# untitled.net
KiCad netlist of a schematic drawn in EAGLE
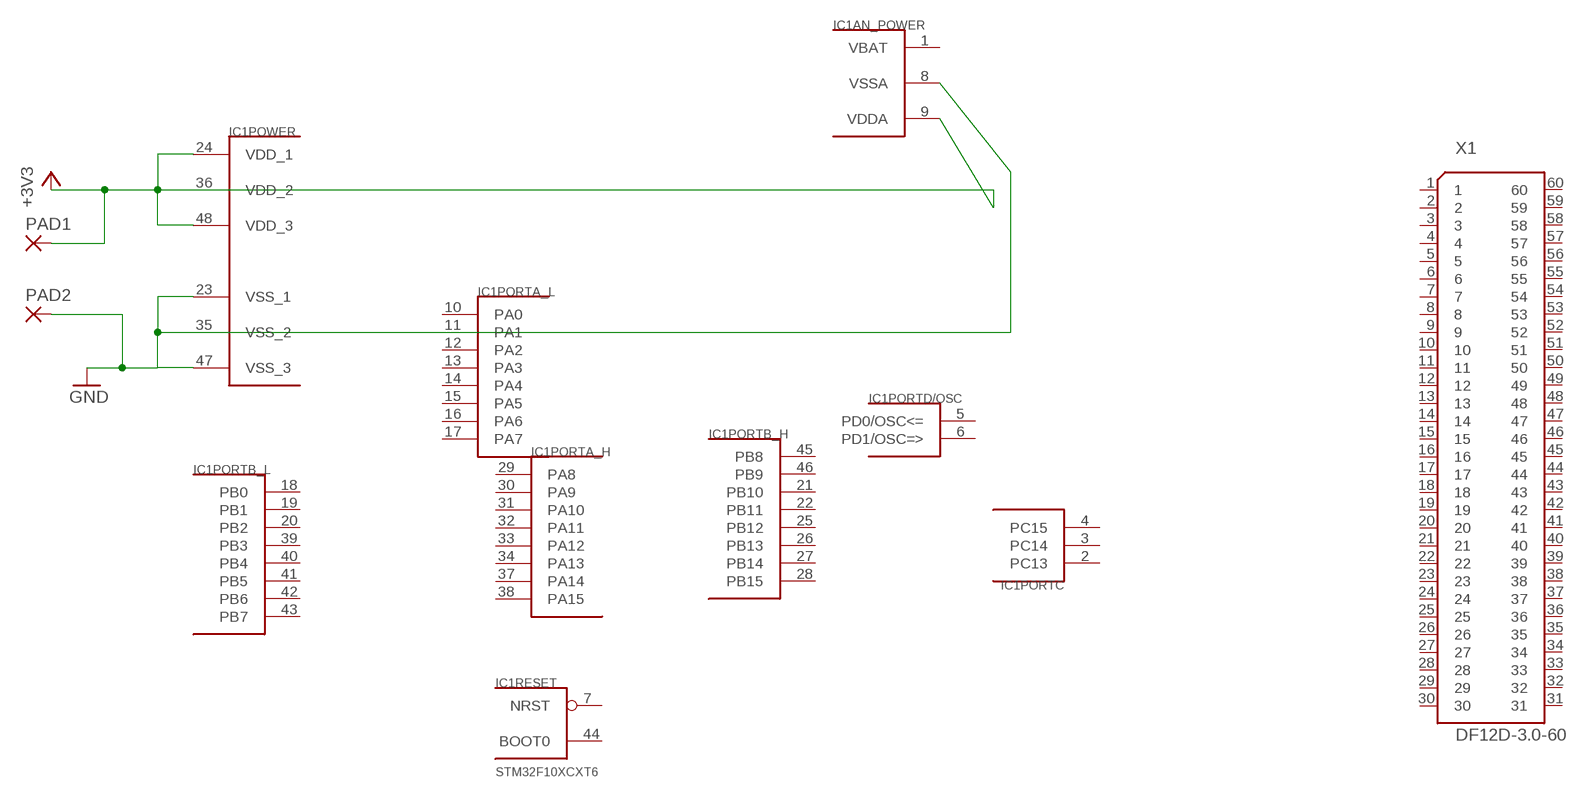
[diagram p0: schematic, sheet 1]

(export (version "E")
  (design (tool "Eeschema 10.0.6"))
  (components
    (comp (ref "IC1")
      (value "STM32F10XCXT6")
      (footprint "eagle-import:TQFP48")
      (libsource (lib "eagle-import") (part "STM32F10XCXT6"))
    )
    (comp (ref "PAD1")
      (value "1,6/0,8")
      (footprint "eagle-import:1,6_0,8")
      (libsource (lib "eagle-import") (part "1,6/0,8"))
    )
    (comp (ref "PAD2")
      (value "1,6/0,8")
      (footprint "eagle-import:1,6_0,8")
      (libsource (lib "eagle-import") (part "1,6/0,8"))
    )
    (comp (ref "X1")
      (value "DF12D-3.0-60")
      (footprint "eagle-import:DF12-3.0-60")
      (libsource (lib "eagle-import") (part "DF12D-3.0-60"))
    )
  )
  (nets
    (net (code "1") (name "+3V3") (class "Default")
      (node (ref "IC1") (pin "24") (pinfunction "VDD_1_24") (pintype "power_in"))
      (node (ref "IC1") (pin "36") (pinfunction "VDD_2_36") (pintype "power_in"))
      (node (ref "IC1") (pin "48") (pinfunction "VDD_3_48") (pintype "power_in"))
      (node (ref "IC1") (pin "9") (pinfunction "VDDA_9") (pintype "power_in"))
      (node (ref "PAD1") (pin "1") (pinfunction "P_1") (pintype "passive"))
    )
    (net (code "2") (name "/VBAT") (class "Default")
      (node (ref "IC1") (pin "1") (pinfunction "VBAT_1") (pintype "power_in"))
    )
    (net (code "3") (name "GND") (class "Default")
      (node (ref "IC1") (pin "23") (pinfunction "VSS_1_23") (pintype "power_in"))
      (node (ref "IC1") (pin "35") (pinfunction "VSS_2_35") (pintype "power_in"))
      (node (ref "IC1") (pin "47") (pinfunction "VSS_3_47") (pintype "power_in"))
      (node (ref "IC1") (pin "8") (pinfunction "VSSA_8") (pintype "power_in"))
      (node (ref "PAD2") (pin "1") (pinfunction "P_1") (pintype "passive"))
    )
    (net (code "4") (name "unconnected-(IC1B-PA8-Pad29)") (class "Default")
      (node (ref "IC1") (pin "29") (pinfunction "PA8_29") (pintype "bidirectional"))
    )
    (net (code "5") (name "unconnected-(IC1B-PA9-Pad30)") (class "Default")
      (node (ref "IC1") (pin "30") (pinfunction "PA9_30") (pintype "bidirectional"))
    )
    (net (code "6") (name "unconnected-(IC1B-PA10-Pad31)") (class "Default")
      (node (ref "IC1") (pin "31") (pinfunction "PA10_31") (pintype "bidirectional"))
    )
    (net (code "7") (name "unconnected-(IC1B-PA11-Pad32)") (class "Default")
      (node (ref "IC1") (pin "32") (pinfunction "PA11_32") (pintype "bidirectional"))
    )
    (net (code "8") (name "unconnected-(IC1B-PA12-Pad33)") (class "Default")
      (node (ref "IC1") (pin "33") (pinfunction "PA12_33") (pintype "bidirectional"))
    )
    (net (code "9") (name "unconnected-(IC1B-PA13-Pad34)") (class "Default")
      (node (ref "IC1") (pin "34") (pinfunction "PA13_34") (pintype "bidirectional"))
    )
    (net (code "10") (name "unconnected-(IC1B-PA14-Pad37)") (class "Default")
      (node (ref "IC1") (pin "37") (pinfunction "PA14_37") (pintype "bidirectional"))
    )
    (net (code "11") (name "unconnected-(IC1B-PA15-Pad38)") (class "Default")
      (node (ref "IC1") (pin "38") (pinfunction "PA15_38") (pintype "bidirectional"))
    )
    (net (code "12") (name "unconnected-(IC1C-PA0-Pad10)") (class "Default")
      (node (ref "IC1") (pin "10") (pinfunction "PA0_10") (pintype "bidirectional"))
    )
    (net (code "13") (name "unconnected-(IC1C-PA1-Pad11)") (class "Default")
      (node (ref "IC1") (pin "11") (pinfunction "PA1_11") (pintype "bidirectional"))
    )
    (net (code "14") (name "unconnected-(IC1C-PA2-Pad12)") (class "Default")
      (node (ref "IC1") (pin "12") (pinfunction "PA2_12") (pintype "bidirectional"))
    )
    (net (code "15") (name "unconnected-(IC1C-PA3-Pad13)") (class "Default")
      (node (ref "IC1") (pin "13") (pinfunction "PA3_13") (pintype "bidirectional"))
    )
    (net (code "16") (name "unconnected-(IC1C-PA4-Pad14)") (class "Default")
      (node (ref "IC1") (pin "14") (pinfunction "PA4_14") (pintype "bidirectional"))
    )
    (net (code "17") (name "unconnected-(IC1C-PA5-Pad15)") (class "Default")
      (node (ref "IC1") (pin "15") (pinfunction "PA5_15") (pintype "bidirectional"))
    )
    (net (code "18") (name "unconnected-(IC1C-PA6-Pad16)") (class "Default")
      (node (ref "IC1") (pin "16") (pinfunction "PA6_16") (pintype "bidirectional"))
    )
    (net (code "19") (name "unconnected-(IC1C-PA7-Pad17)") (class "Default")
      (node (ref "IC1") (pin "17") (pinfunction "PA7_17") (pintype "bidirectional"))
    )
    (net (code "20") (name "unconnected-(IC1D-PB8-Pad45)") (class "Default")
      (node (ref "IC1") (pin "45") (pinfunction "PB8_45") (pintype "bidirectional"))
    )
    (net (code "21") (name "unconnected-(IC1D-PB9-Pad46)") (class "Default")
      (node (ref "IC1") (pin "46") (pinfunction "PB9_46") (pintype "bidirectional"))
    )
    (net (code "22") (name "unconnected-(IC1D-PB10-Pad21)") (class "Default")
      (node (ref "IC1") (pin "21") (pinfunction "PB10_21") (pintype "bidirectional"))
    )
    (net (code "23") (name "unconnected-(IC1D-PB11-Pad22)") (class "Default")
      (node (ref "IC1") (pin "22") (pinfunction "PB11_22") (pintype "bidirectional"))
    )
    (net (code "24") (name "unconnected-(IC1D-PB12-Pad25)") (class "Default")
      (node (ref "IC1") (pin "25") (pinfunction "PB12_25") (pintype "bidirectional"))
    )
    (net (code "25") (name "unconnected-(IC1D-PB13-Pad26)") (class "Default")
      (node (ref "IC1") (pin "26") (pinfunction "PB13_26") (pintype "bidirectional"))
    )
    (net (code "26") (name "unconnected-(IC1D-PB14-Pad27)") (class "Default")
      (node (ref "IC1") (pin "27") (pinfunction "PB14_27") (pintype "bidirectional"))
    )
    (net (code "27") (name "unconnected-(IC1D-PB15-Pad28)") (class "Default")
      (node (ref "IC1") (pin "28") (pinfunction "PB15_28") (pintype "bidirectional"))
    )
    (net (code "28") (name "unconnected-(IC1E-PB0-Pad18)") (class "Default")
      (node (ref "IC1") (pin "18") (pinfunction "PB0_18") (pintype "bidirectional"))
    )
    (net (code "29") (name "unconnected-(IC1E-PB1-Pad19)") (class "Default")
      (node (ref "IC1") (pin "19") (pinfunction "PB1_19") (pintype "bidirectional"))
    )
    (net (code "30") (name "unconnected-(IC1E-PB2-Pad20)") (class "Default")
      (node (ref "IC1") (pin "20") (pinfunction "PB2_20") (pintype "bidirectional"))
    )
    (net (code "31") (name "unconnected-(IC1E-PB3-Pad39)") (class "Default")
      (node (ref "IC1") (pin "39") (pinfunction "PB3_39") (pintype "bidirectional"))
    )
    (net (code "32") (name "unconnected-(IC1E-PB4-Pad40)") (class "Default")
      (node (ref "IC1") (pin "40") (pinfunction "PB4_40") (pintype "bidirectional"))
    )
    (net (code "33") (name "unconnected-(IC1E-PB5-Pad41)") (class "Default")
      (node (ref "IC1") (pin "41") (pinfunction "PB5_41") (pintype "bidirectional"))
    )
    (net (code "34") (name "unconnected-(IC1E-PB6-Pad42)") (class "Default")
      (node (ref "IC1") (pin "42") (pinfunction "PB6_42") (pintype "bidirectional"))
    )
    (net (code "35") (name "unconnected-(IC1E-PB7-Pad43)") (class "Default")
      (node (ref "IC1") (pin "43") (pinfunction "PB7_43") (pintype "bidirectional"))
    )
    (net (code "36") (name "unconnected-(IC1F-PC13-Pad2)") (class "Default")
      (node (ref "IC1") (pin "2") (pinfunction "PC13_2") (pintype "bidirectional"))
    )
    (net (code "37") (name "unconnected-(IC1F-PC14-Pad3)") (class "Default")
      (node (ref "IC1") (pin "3") (pinfunction "PC14_3") (pintype "bidirectional"))
    )
    (net (code "38") (name "unconnected-(IC1F-PC15-Pad4)") (class "Default")
      (node (ref "IC1") (pin "4") (pinfunction "PC15_4") (pintype "bidirectional"))
    )
    (net (code "39") (name "unconnected-(IC1G-PD0{slash}OSC<=-Pad5)") (class "Default")
      (node (ref "IC1") (pin "5") (pinfunction "PD0/OSC<=_5") (pintype "bidirectional"))
    )
    (net (code "40") (name "unconnected-(IC1G-PD1{slash}OSC=>-Pad6)") (class "Default")
      (node (ref "IC1") (pin "6") (pinfunction "PD1/OSC=>_6") (pintype "bidirectional"))
    )
    (net (code "41") (name "unconnected-(IC1I-BOOT0-Pad44)") (class "Default")
      (node (ref "IC1") (pin "44") (pinfunction "BOOT0_44") (pintype "input"))
    )
    (net (code "42") (name "unconnected-(IC1I-NRST-Pad7)") (class "Default")
      (node (ref "IC1") (pin "7") (pinfunction "NRST_7") (pintype "input"))
    )
    (net (code "43") (name "unconnected-(X1-Pad1)") (class "Default")
      (node (ref "X1") (pin "1") (pinfunction "1_1") (pintype "bidirectional"))
    )
    (net (code "44") (name "unconnected-(X1-Pad2)") (class "Default")
      (node (ref "X1") (pin "2") (pinfunction "2_2") (pintype "bidirectional"))
    )
    (net (code "45") (name "unconnected-(X1-Pad3)") (class "Default")
      (node (ref "X1") (pin "3") (pinfunction "3_3") (pintype "bidirectional"))
    )
    (net (code "46") (name "unconnected-(X1-Pad4)") (class "Default")
      (node (ref "X1") (pin "4") (pinfunction "4_4") (pintype "bidirectional"))
    )
    (net (code "47") (name "unconnected-(X1-Pad5)") (class "Default")
      (node (ref "X1") (pin "5") (pinfunction "5_5") (pintype "bidirectional"))
    )
    (net (code "48") (name "unconnected-(X1-Pad6)") (class "Default")
      (node (ref "X1") (pin "6") (pinfunction "6_6") (pintype "bidirectional"))
    )
    (net (code "49") (name "unconnected-(X1-Pad7)") (class "Default")
      (node (ref "X1") (pin "7") (pinfunction "7_7") (pintype "bidirectional"))
    )
    (net (code "50") (name "unconnected-(X1-Pad8)") (class "Default")
      (node (ref "X1") (pin "8") (pinfunction "8_8") (pintype "bidirectional"))
    )
    (net (code "51") (name "unconnected-(X1-Pad9)") (class "Default")
      (node (ref "X1") (pin "9") (pinfunction "9_9") (pintype "bidirectional"))
    )
    (net (code "52") (name "unconnected-(X1-Pad10)") (class "Default")
      (node (ref "X1") (pin "10") (pinfunction "10_10") (pintype "bidirectional"))
    )
    (net (code "53") (name "unconnected-(X1-Pad11)") (class "Default")
      (node (ref "X1") (pin "11") (pinfunction "11_11") (pintype "bidirectional"))
    )
    (net (code "54") (name "unconnected-(X1-Pad12)") (class "Default")
      (node (ref "X1") (pin "12") (pinfunction "12_12") (pintype "bidirectional"))
    )
    (net (code "55") (name "unconnected-(X1-Pad13)") (class "Default")
      (node (ref "X1") (pin "13") (pinfunction "13_13") (pintype "bidirectional"))
    )
    (net (code "56") (name "unconnected-(X1-Pad14)") (class "Default")
      (node (ref "X1") (pin "14") (pinfunction "14_14") (pintype "bidirectional"))
    )
    (net (code "57") (name "unconnected-(X1-Pad15)") (class "Default")
      (node (ref "X1") (pin "15") (pinfunction "15_15") (pintype "bidirectional"))
    )
    (net (code "58") (name "unconnected-(X1-Pad16)") (class "Default")
      (node (ref "X1") (pin "16") (pinfunction "16_16") (pintype "bidirectional"))
    )
    (net (code "59") (name "unconnected-(X1-Pad17)") (class "Default")
      (node (ref "X1") (pin "17") (pinfunction "17_17") (pintype "bidirectional"))
    )
    (net (code "60") (name "unconnected-(X1-Pad18)") (class "Default")
      (node (ref "X1") (pin "18") (pinfunction "18_18") (pintype "bidirectional"))
    )
    (net (code "61") (name "unconnected-(X1-Pad19)") (class "Default")
      (node (ref "X1") (pin "19") (pinfunction "19_19") (pintype "bidirectional"))
    )
    (net (code "62") (name "unconnected-(X1-Pad20)") (class "Default")
      (node (ref "X1") (pin "20") (pinfunction "20_20") (pintype "bidirectional"))
    )
    (net (code "63") (name "unconnected-(X1-Pad21)") (class "Default")
      (node (ref "X1") (pin "21") (pinfunction "21_21") (pintype "bidirectional"))
    )
    (net (code "64") (name "unconnected-(X1-Pad22)") (class "Default")
      (node (ref "X1") (pin "22") (pinfunction "22_22") (pintype "bidirectional"))
    )
    (net (code "65") (name "unconnected-(X1-Pad23)") (class "Default")
      (node (ref "X1") (pin "23") (pinfunction "23_23") (pintype "bidirectional"))
    )
    (net (code "66") (name "unconnected-(X1-Pad24)") (class "Default")
      (node (ref "X1") (pin "24") (pinfunction "24_24") (pintype "bidirectional"))
    )
    (net (code "67") (name "unconnected-(X1-Pad25)") (class "Default")
      (node (ref "X1") (pin "25") (pinfunction "25_25") (pintype "bidirectional"))
    )
    (net (code "68") (name "unconnected-(X1-Pad26)") (class "Default")
      (node (ref "X1") (pin "26") (pinfunction "26_26") (pintype "bidirectional"))
    )
    (net (code "69") (name "unconnected-(X1-Pad27)") (class "Default")
      (node (ref "X1") (pin "27") (pinfunction "27_27") (pintype "bidirectional"))
    )
    (net (code "70") (name "unconnected-(X1-Pad28)") (class "Default")
      (node (ref "X1") (pin "28") (pinfunction "28_28") (pintype "bidirectional"))
    )
    (net (code "71") (name "unconnected-(X1-Pad29)") (class "Default")
      (node (ref "X1") (pin "29") (pinfunction "29_29") (pintype "bidirectional"))
    )
    (net (code "72") (name "unconnected-(X1-Pad30)") (class "Default")
      (node (ref "X1") (pin "30") (pinfunction "30_30") (pintype "bidirectional"))
    )
    (net (code "73") (name "unconnected-(X1-Pad31)") (class "Default")
      (node (ref "X1") (pin "31") (pinfunction "31_31") (pintype "bidirectional"))
    )
    (net (code "74") (name "unconnected-(X1-Pad32)") (class "Default")
      (node (ref "X1") (pin "32") (pinfunction "32_32") (pintype "bidirectional"))
    )
    (net (code "75") (name "unconnected-(X1-Pad33)") (class "Default")
      (node (ref "X1") (pin "33") (pinfunction "33_33") (pintype "bidirectional"))
    )
    (net (code "76") (name "unconnected-(X1-Pad34)") (class "Default")
      (node (ref "X1") (pin "34") (pinfunction "34_34") (pintype "bidirectional"))
    )
    (net (code "77") (name "unconnected-(X1-Pad35)") (class "Default")
      (node (ref "X1") (pin "35") (pinfunction "35_35") (pintype "bidirectional"))
    )
    (net (code "78") (name "unconnected-(X1-Pad36)") (class "Default")
      (node (ref "X1") (pin "36") (pinfunction "36_36") (pintype "bidirectional"))
    )
    (net (code "79") (name "unconnected-(X1-Pad37)") (class "Default")
      (node (ref "X1") (pin "37") (pinfunction "37_37") (pintype "bidirectional"))
    )
    (net (code "80") (name "unconnected-(X1-Pad38)") (class "Default")
      (node (ref "X1") (pin "38") (pinfunction "38_38") (pintype "bidirectional"))
    )
    (net (code "81") (name "unconnected-(X1-Pad39)") (class "Default")
      (node (ref "X1") (pin "39") (pinfunction "39_39") (pintype "bidirectional"))
    )
    (net (code "82") (name "unconnected-(X1-Pad40)") (class "Default")
      (node (ref "X1") (pin "40") (pinfunction "40_40") (pintype "bidirectional"))
    )
    (net (code "83") (name "unconnected-(X1-Pad41)") (class "Default")
      (node (ref "X1") (pin "41") (pinfunction "41_41") (pintype "bidirectional"))
    )
    (net (code "84") (name "unconnected-(X1-Pad42)") (class "Default")
      (node (ref "X1") (pin "42") (pinfunction "42_42") (pintype "bidirectional"))
    )
    (net (code "85") (name "unconnected-(X1-Pad43)") (class "Default")
      (node (ref "X1") (pin "43") (pinfunction "43_43") (pintype "bidirectional"))
    )
    (net (code "86") (name "unconnected-(X1-Pad44)") (class "Default")
      (node (ref "X1") (pin "44") (pinfunction "44_44") (pintype "bidirectional"))
    )
    (net (code "87") (name "unconnected-(X1-Pad45)") (class "Default")
      (node (ref "X1") (pin "45") (pinfunction "45_45") (pintype "bidirectional"))
    )
    (net (code "88") (name "unconnected-(X1-Pad46)") (class "Default")
      (node (ref "X1") (pin "46") (pinfunction "46_46") (pintype "bidirectional"))
    )
    (net (code "89") (name "unconnected-(X1-Pad47)") (class "Default")
      (node (ref "X1") (pin "47") (pinfunction "47_47") (pintype "bidirectional"))
    )
    (net (code "90") (name "unconnected-(X1-Pad48)") (class "Default")
      (node (ref "X1") (pin "48") (pinfunction "48_48") (pintype "bidirectional"))
    )
    (net (code "91") (name "unconnected-(X1-Pad49)") (class "Default")
      (node (ref "X1") (pin "49") (pinfunction "49_49") (pintype "bidirectional"))
    )
    (net (code "92") (name "unconnected-(X1-Pad50)") (class "Default")
      (node (ref "X1") (pin "50") (pinfunction "50_50") (pintype "bidirectional"))
    )
    (net (code "93") (name "unconnected-(X1-Pad51)") (class "Default")
      (node (ref "X1") (pin "51") (pinfunction "51_51") (pintype "bidirectional"))
    )
    (net (code "94") (name "unconnected-(X1-Pad52)") (class "Default")
      (node (ref "X1") (pin "52") (pinfunction "52_52") (pintype "bidirectional"))
    )
    (net (code "95") (name "unconnected-(X1-Pad53)") (class "Default")
      (node (ref "X1") (pin "53") (pinfunction "53_53") (pintype "bidirectional"))
    )
    (net (code "96") (name "unconnected-(X1-Pad54)") (class "Default")
      (node (ref "X1") (pin "54") (pinfunction "54_54") (pintype "bidirectional"))
    )
    (net (code "97") (name "unconnected-(X1-Pad55)") (class "Default")
      (node (ref "X1") (pin "55") (pinfunction "55_55") (pintype "bidirectional"))
    )
    (net (code "98") (name "unconnected-(X1-Pad56)") (class "Default")
      (node (ref "X1") (pin "56") (pinfunction "56_56") (pintype "bidirectional"))
    )
    (net (code "99") (name "unconnected-(X1-Pad57)") (class "Default")
      (node (ref "X1") (pin "57") (pinfunction "57_57") (pintype "bidirectional"))
    )
    (net (code "100") (name "unconnected-(X1-Pad58)") (class "Default")
      (node (ref "X1") (pin "58") (pinfunction "58_58") (pintype "bidirectional"))
    )
    (net (code "101") (name "unconnected-(X1-Pad59)") (class "Default")
      (node (ref "X1") (pin "59") (pinfunction "59_59") (pintype "bidirectional"))
    )
    (net (code "102") (name "unconnected-(X1-Pad60)") (class "Default")
      (node (ref "X1") (pin "60") (pinfunction "60_60") (pintype "bidirectional"))
    )
  )
)
